# 1_PWR_1.net
KiCad netlist of a schematic drawn in Altium Designer
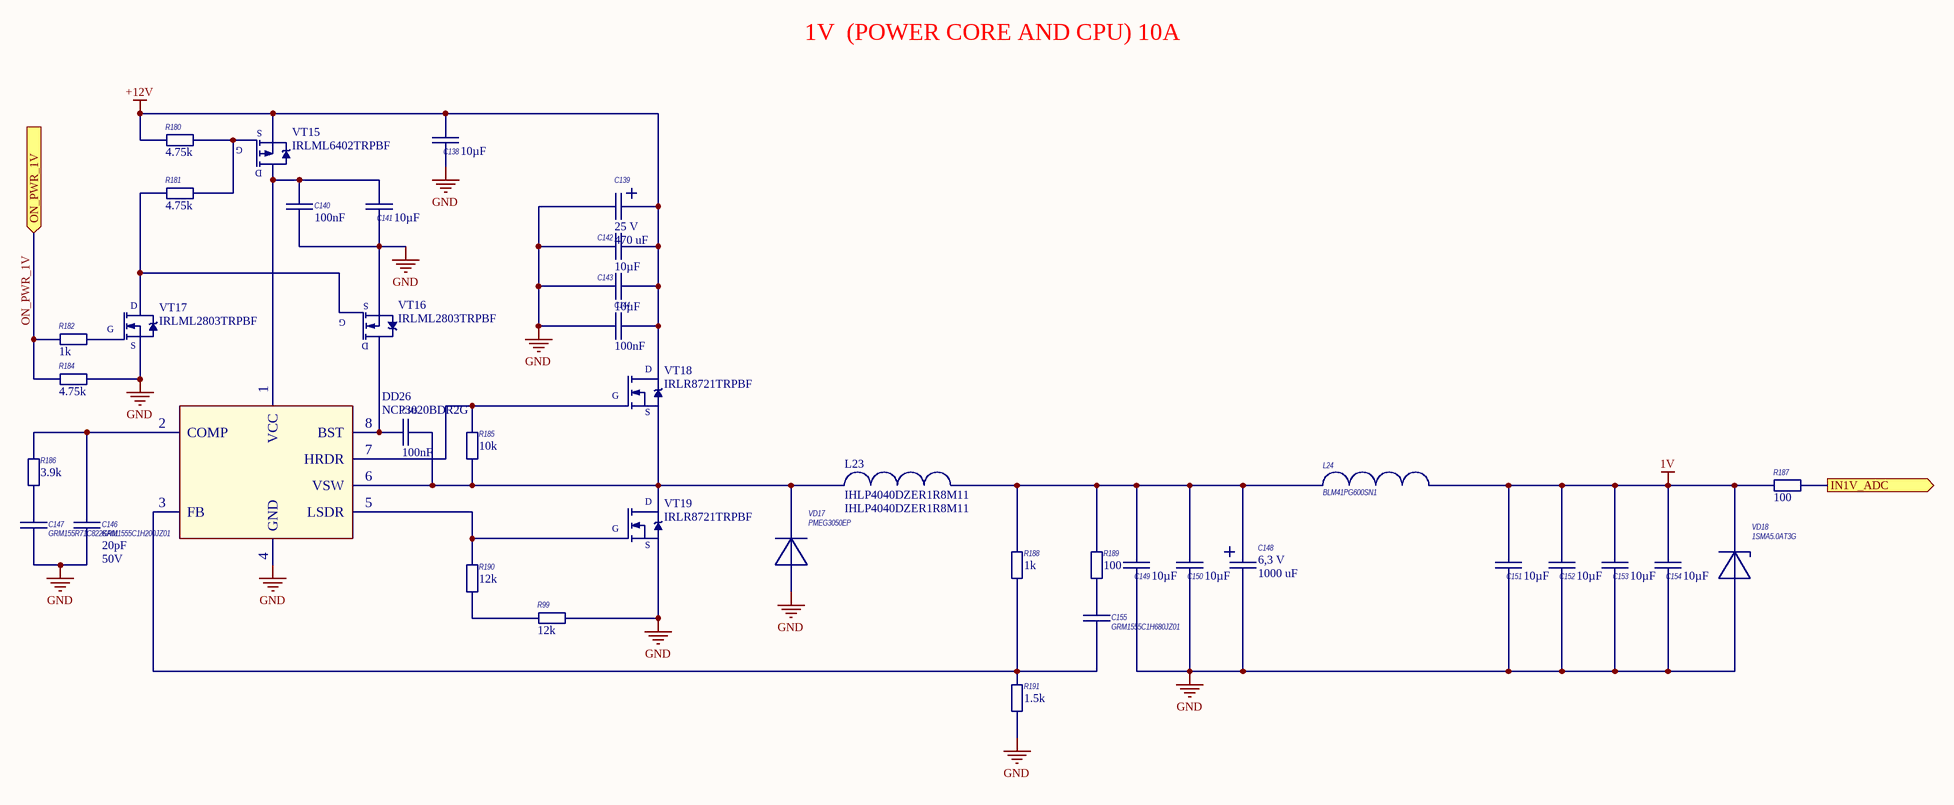
[diagram p0: 1_PWR_1.SchDoc]

(export (version "E")
  (design (tool "Eeschema 10.0.6"))
  (components
    (comp (ref "C138")
      (value "GRM21BR61C106KE15")
      (footprint "CAPC2012[0805]")
      (description "C0805, 10uF 10%, 16V, X5R")
      (fields
        (field (name "MANUFACTURER") "Murata")
        (field (name "TOLERANCE") "±10%")
        (field (name "CAPACITANCE") "10µF")
      )
      (libsource (lib "CAPACITORS") (part "GRM21BR61C106KE15"))
    )
    (comp (ref "C139")
      (value "CA025M0470REG-1010")
      (footprint "CAP SMD 1010")
      (description "Capacitor Aluminium SMD1010, 470uF 25V")
      (fields
        (field (name "MANUFACTURER") "Yageo")
        (field (name "TOLERANCE") "20 %")
        (field (name "VOLTAGE RATING") "25 V")
        (field (name "CAPACITANCE") "470 uF")
      )
      (libsource (lib "CAPACITORS") (part "CA025M0470REG-1010"))
    )
    (comp (ref "C140")
      (value "GRM155R71E104KE14D")
      (footprint "C0402_IPC High Density")
      (description "C0402, 100nF, 25V, X7R")
      (fields
        (field (name "MANUFACTURER") "Murata")
        (field (name "CAPACITANCE") "100nF")
        (field (name "CUSTOMER PART NUMBER") "Конденсатор, 100n, 0402, 25V, X7R, 10%")
      )
      (libsource (lib "CAPACITORS") (part "GRM155R71E104KE14D"))
    )
    (comp (ref "C141")
      (value "GRM21BR61C106KE15")
      (footprint "CAPC2012[0805]")
      (description "C0805, 10uF 10%, 16V, X5R")
      (fields
        (field (name "MANUFACTURER") "Murata")
        (field (name "TOLERANCE") "±10%")
        (field (name "CAPACITANCE") "10µF")
      )
      (libsource (lib "CAPACITORS") (part "GRM21BR61C106KE15"))
    )
    (comp (ref "C142")
      (value "GRM21BR61C106KE15")
      (footprint "CAPC2012[0805]")
      (description "C0805, 10uF 10%, 16V, X5R")
      (fields
        (field (name "MANUFACTURER") "Murata")
        (field (name "TOLERANCE") "±10%")
        (field (name "CAPACITANCE") "10µF")
      )
      (libsource (lib "CAPACITORS") (part "GRM21BR61C106KE15"))
    )
    (comp (ref "C143")
      (value "GRM21BR61C106KE15")
      (footprint "CAPC2012[0805]")
      (description "C0805, 10uF 10%, 16V, X5R")
      (fields
        (field (name "MANUFACTURER") "Murata")
        (field (name "TOLERANCE") "±10%")
        (field (name "CAPACITANCE") "10µF")
      )
      (libsource (lib "CAPACITORS") (part "GRM21BR61C106KE15"))
    )
    (comp (ref "C144")
      (value "GRM155R71E104KE14D")
      (footprint "C0402_IPC High Density")
      (description "C0402, 100nF, 25V, X7R")
      (fields
        (field (name "MANUFACTURER") "Murata")
        (field (name "CAPACITANCE") "100nF")
        (field (name "CUSTOMER PART NUMBER") "Конденсатор, 100n, 0402, 25V, X7R, 10%")
      )
      (libsource (lib "CAPACITORS") (part "GRM155R71E104KE14D"))
    )
    (comp (ref "C145")
      (value "GRM155R71E104KE14D")
      (footprint "C0402_IPC High Density")
      (description "C0402, 100nF, 25V, X7R")
      (fields
        (field (name "CAPACITANCE") "100nF")
        (field (name "CUSTOMER PART NUMBER") "Конденсатор, 100n, 0402, 25V, X7R, 10%")
        (field (name "MANUFACTURER") "Murata")
      )
      (libsource (lib "CAPACITORS") (part "GRM155R71E104KE14D"))
    )
    (comp (ref "C146")
      (value "GRM1555C1H200JZ01")
      (footprint "CAPC1005[0402]")
      (description "C0402, 20pF,  50V, C0G")
      (fields
        (field (name "MANUFACTURER") "Murata")
        (field (name "TOLERANCE") "±5%")
        (field (name "CAPACITANCE") "20pF")
        (field (name "VOLTAGE - RATED") "50V")
      )
      (libsource (lib "CAPACITORS") (part "GRM1555C1H200JZ01"))
    )
    (comp (ref "C147")
      (value "GRM155R71C822KA01")
      (footprint "CAPC1005[0402]")
      (description "C0402, 8.2nF,  50V, X7R")
      (fields (field (name "MANUFACTURER") "Murata") (field (name "TOLERANCE") "10 %"))
      (libsource (lib "CAPACITORS") (part "GRM155R71C822KA01"))
    )
    (comp (ref "C148")
      (value "CA006M1000REG-1010")
      (footprint "CAP SMD 1010")
      (description "Capacitor Aluminium SMD1010, 1000uF 6,3V")
      (fields
        (field (name "MANUFACTURER") "Yageo")
        (field (name "TOLERANCE") "20 %")
        (field (name "VOLTAGE RATING") "6,3 V")
        (field (name "CAPACITANCE") "1000 uF")
      )
      (libsource (lib "CAPACITORS") (part "CA006M1000REG-1010"))
    )
    (comp (ref "C149")
      (value "GRM21BR61C106KE15")
      (footprint "CAPC2012[0805]")
      (description "C0805, 10uF 10%, 16V, X5R")
      (fields
        (field (name "MANUFACTURER") "Murata")
        (field (name "TOLERANCE") "±10%")
        (field (name "CAPACITANCE") "10µF")
      )
      (libsource (lib "CAPACITORS") (part "GRM21BR61C106KE15"))
    )
    (comp (ref "C150")
      (value "GRM21BR61C106KE15")
      (footprint "CAPC2012[0805]")
      (description "C0805, 10uF 10%, 16V, X5R")
      (fields
        (field (name "MANUFACTURER") "Murata")
        (field (name "TOLERANCE") "±10%")
        (field (name "CAPACITANCE") "10µF")
      )
      (libsource (lib "CAPACITORS") (part "GRM21BR61C106KE15"))
    )
    (comp (ref "C151")
      (value "GRM21BR61C106KE15")
      (footprint "CAPC2012[0805]")
      (description "C0805, 10uF 10%, 16V, X5R")
      (fields
        (field (name "MANUFACTURER") "Murata")
        (field (name "TOLERANCE") "±10%")
        (field (name "CAPACITANCE") "10µF")
      )
      (libsource (lib "CAPACITORS") (part "GRM21BR61C106KE15"))
    )
    (comp (ref "C152")
      (value "GRM21BR61C106KE15")
      (footprint "CAPC2012[0805]")
      (description "C0805, 10uF 10%, 16V, X5R")
      (fields
        (field (name "MANUFACTURER") "Murata")
        (field (name "TOLERANCE") "±10%")
        (field (name "CAPACITANCE") "10µF")
      )
      (libsource (lib "CAPACITORS") (part "GRM21BR61C106KE15"))
    )
    (comp (ref "C153")
      (value "GRM21BR61C106KE15")
      (footprint "CAPC2012[0805]")
      (description "C0805, 10uF 10%, 16V, X5R")
      (fields
        (field (name "MANUFACTURER") "Murata")
        (field (name "TOLERANCE") "±10%")
        (field (name "CAPACITANCE") "10µF")
      )
      (libsource (lib "CAPACITORS") (part "GRM21BR61C106KE15"))
    )
    (comp (ref "C154")
      (value "GRM21BR61C106KE15")
      (footprint "CAPC2012[0805]")
      (description "C0805, 10uF 10%, 16V, X5R")
      (fields
        (field (name "MANUFACTURER") "Murata")
        (field (name "TOLERANCE") "±10%")
        (field (name "CAPACITANCE") "10µF")
      )
      (libsource (lib "CAPACITORS") (part "GRM21BR61C106KE15"))
    )
    (comp (ref "C155")
      (value "GRM1555C1H680JZ01")
      (footprint "CAPC1005[0402]")
      (description "C0402, 68pF,  50V, C0G")
      (fields (field (name "TOLERANCE") "±5%") (field (name "MANUFACTURER") "Murata"))
      (libsource (lib "CAPACITORS") (part "GRM1555C1H680JZ01"))
    )
    (comp (ref "DD26")
      (value "NCP3020BDR2G")
      (footprint "751-07_N")
      (description "IC PWM Controller 600 kHz NCP3020BDR2G")
      (fields
        (field (name "MANUFACTURER") "ON Semiconductor")
        (field (name "CUSTOMER PART NUMBER") "Микросхема, NCP3020BDR2G, IC REG CTRLR BUCK, 8-SOIC")
      )
      (libsource (lib "DIGITAL and ANALIG ICs") (part "NCP3020BDR2G"))
    )
    (comp (ref "L23")
      (value "IHLP4040DZER1R8M11")
      (footprint "IHLP4040DZ")
      (description "INDUCTOR 1.8UH 16A")
      (fields
        (field (name "MANUFACTURER") "Vishay Dale")
        (field (name "TOLERANCE") "±20%")
        (field (name "MANUFACTURER PART NUMBER") "IHLP4040DZER1R8M11")
      )
      (libsource (lib "INDUCTORS") (part "IHLP4040DZER1R8M11"))
    )
    (comp (ref "L24")
      (value "BLM41PG600SN1")
      (footprint "INDUCTORS:BLM41P")
      (description "FILTER BLM41 (1806, 6A)")
      (fields
        (field (name "MANUFACTURER") "Murata")
        (field (name "MANUFACTURER PART NUMBER") "BLM41PG600SN1L")
      )
      (libsource (lib "INDUCTORS") (part "BLM41PG600SN1"))
    )
    (comp (ref "R99")
      (value "ERJ-2RKF1202X")
      (footprint "R0402_IPC High Density")
      (description "R0402, 12k 1%")
      (fields
        (field (name "MANUFACTURER") "Panasonic")
        (field (name "TOLERANCE") "±1%")
        (field (name "RESISTANCE (OHMS)") "12k")
      )
      (libsource (lib "RESISTOR") (part "ERJ-2RKF1202X"))
    )
    (comp (ref "R180")
      (value "ERJ-2RKF4751X")
      (footprint "R0402_IPC High Density")
      (description "R0402, 4.75k 1%")
      (fields
        (field (name "TOLERANCE") "±1%")
        (field (name "MANUFACTURER") "Panasonic")
        (field (name "RESISTANCE (OHMS)") "4.75k")
      )
      (libsource (lib "RESISTOR") (part "ERJ-2RKF4751X"))
    )
    (comp (ref "R181")
      (value "ERJ-2RKF4751X")
      (footprint "R0402_IPC High Density")
      (description "R0402, 4.75k 1%")
      (fields
        (field (name "TOLERANCE") "±1%")
        (field (name "MANUFACTURER") "Panasonic")
        (field (name "RESISTANCE (OHMS)") "4.75k")
      )
      (libsource (lib "RESISTOR") (part "ERJ-2RKF4751X"))
    )
    (comp (ref "R182")
      (value "ERJ-2RKF1001X")
      (footprint "R0402_IPC High Density")
      (description "R0402, 1k 1%")
      (fields
        (field (name "MANUFACTURER") "Panasonic")
        (field (name "TOLERANCE") "1 %")
        (field (name "RESISTANCE") "1k")
      )
      (libsource (lib "RESISTOR") (part "ERJ-2RKF1001X"))
    )
    (comp (ref "R184")
      (value "ERJ-2RKF4751X")
      (footprint "R0402_IPC High Density")
      (description "R0402, 4.75k 1%")
      (fields
        (field (name "TOLERANCE") "±1%")
        (field (name "MANUFACTURER") "Panasonic")
        (field (name "RESISTANCE (OHMS)") "4.75k")
      )
      (libsource (lib "RESISTOR") (part "ERJ-2RKF4751X"))
    )
    (comp (ref "R185")
      (value "ERJ-2RKF1002X")
      (footprint "R0402_IPC High Density")
      (description "R0402, 10k 1%")
      (fields
        (field (name "MANUFACTURER") "Panasonic")
        (field (name "TOLERANCE") "1 %")
        (field (name "RESISTANCE") "10k")
      )
      (libsource (lib "RESISTOR") (part "ERJ-2RKF1002X"))
    )
    (comp (ref "R186")
      (value "ERJ-2RKF3901X")
      (footprint "R0402_IPC High Density")
      (description "R0402, 3.9k 1%")
      (fields
        (field (name "MANUFACTURER") "Panasonic")
        (field (name "TOLERANCE") "1 %")
        (field (name "RESISTANCE") "3.9k")
      )
      (libsource (lib "RESISTOR") (part "ERJ-2RKF3901X"))
    )
    (comp (ref "R187")
      (value "ERJ-2RKF1000X")
      (footprint "R0402_IPC High Density")
      (description "R0402, 100R 1%")
      (fields
        (field (name "MANUFACTURER") "Panasonic")
        (field (name "TOLERANCE") "1 %")
        (field (name "RESISTANCE") "100")
      )
      (libsource (lib "RESISTOR") (part "ERJ-2RKF1000X"))
    )
    (comp (ref "R188")
      (value "ERJ-2RKF1001X")
      (footprint "R0402_IPC High Density")
      (description "R0402, 1k 1%")
      (fields
        (field (name "MANUFACTURER") "Panasonic")
        (field (name "TOLERANCE") "1 %")
        (field (name "RESISTANCE") "1k")
      )
      (libsource (lib "RESISTOR") (part "ERJ-2RKF1001X"))
    )
    (comp (ref "R189")
      (value "ERJ-2RKF1000X")
      (footprint "R0402_IPC High Density")
      (description "R0402, 100R 1%")
      (fields
        (field (name "MANUFACTURER") "Panasonic")
        (field (name "TOLERANCE") "1 %")
        (field (name "RESISTANCE") "100")
      )
      (libsource (lib "RESISTOR") (part "ERJ-2RKF1000X"))
    )
    (comp (ref "R190")
      (value "ERJ-2RKF1202X")
      (footprint "R0402_IPC High Density")
      (description "R0402, 12k 1%")
      (fields
        (field (name "MANUFACTURER") "Panasonic")
        (field (name "TOLERANCE") "±1%")
        (field (name "RESISTANCE (OHMS)") "12k")
      )
      (libsource (lib "RESISTOR") (part "ERJ-2RKF1202X"))
    )
    (comp (ref "R191")
      (value "ERJ-2RKF1501X")
      (footprint "R0402_IPC High Density")
      (description "R0402, 1.5k 1%")
      (fields
        (field (name "MANUFACTURER") "Panasonic")
        (field (name "TOLERANCE") "±1%")
        (field (name "RESISTANCE (OHMS)") "1.5k")
      )
      (libsource (lib "RESISTOR") (part "ERJ-2RKF1501X"))
    )
    (comp (ref "VD17")
      (value "PMEG3050EP")
      (footprint "SOD128")
      (description "DIODE 5 A 30 V Schottky barrier rectifier")
      (fields
        (field (name "MANUFACTURER") "NXP Semiconductors")
        (field (name "CUSTOMER PART NUMBER") "Диод, PMEG3050EP.115, DIODE SCHOTTKY 30V 5A, SOD-128")
      )
      (libsource (lib "DIODES") (part "PMEG3050EP"))
    )
    (comp (ref "VD18")
      (value "1SMA5.0AT3G")
      (footprint "DIODES:SMA")
      (description "DIODE TVS 5V 400W SMA")
      (fields
        (field (name "MANUFACTURER") "ON Semiconductor")
        (field (name "CUSTOMER PART NUMBER") "Диод, 1SMA5.0AT3G, TVS DIODE 5VWM 9.2VC SMA")
      )
      (libsource (lib "DIODES") (part "1SMA5.0AT3G"))
    )
    (comp (ref "VT15")
      (value "IRLML6402TRPBF")
      (footprint "SOT-23")
      (description "MOSFET P-CH 20V 3.7A SOT23")
      (fields
        (field (name "MANUFACTURER") "International Rectifier")
        (field (name "RPART NUMBER") "IRLML5203TRPBF ; IRLML6402PbF")
      )
      (libsource (lib "TRANSISTORS") (part "IRLML6402TRPBF"))
    )
    (comp (ref "VT16")
      (value "IRLML2803TRPBF")
      (footprint "SOT-23")
      (description "MOSFET N-CH 30V 1.2A SOT23")
      (fields
        (field (name "MANUFACTURER") "International Rectifier")
        (field (name "RPART NUMBER") "IRLML2402TRPBF ; IRLML2402PBF ; IRLML2803TRPbF")
      )
      (libsource (lib "TRANSISTORS") (part "IRLML2803PBF"))
    )
    (comp (ref "VT17")
      (value "IRLML2803TRPBF")
      (footprint "SOT-23")
      (description "MOSFET N-CH 30V 1.2A SOT23")
      (fields
        (field (name "MANUFACTURER") "International Rectifier")
        (field (name "RPART NUMBER") "IRLML2402TRPBF ; IRLML2402PBF ; IRLML2803TRPbF")
      )
      (libsource (lib "TRANSISTORS") (part "IRLML2803PBF"))
    )
    (comp (ref "VT18")
      (value "IRLR8721TRPBF")
      (footprint "TRANSISTORS:D-PAK (TO-252AA)")
      (description "MOSFET N-CH 30V 65A D-Pak")
      (fields
        (field (name "MANUFACTURER") "International Rectifier")
        (field (name "CUSTOMER PART NUMBER") "Транзистор, IRLR8721TRPBF, MOSFET N-CH 30V 65A, D-Pak")
      )
      (libsource (lib "TRANSISTORS") (part "IRLR8721PbF"))
    )
    (comp (ref "VT19")
      (value "IRLR8721TRPBF")
      (footprint "TRANSISTORS:D-PAK (TO-252AA)")
      (description "MOSFET N-CH 30V 65A D-Pak")
      (fields
        (field (name "MANUFACTURER") "International Rectifier")
        (field (name "CUSTOMER PART NUMBER") "Транзистор, IRLR8721TRPBF, MOSFET N-CH 30V 65A, D-Pak")
      )
      (libsource (lib "TRANSISTORS") (part "IRLR8721PbF"))
    )
  )
  (nets
    (net (code "1") (name "+12V") (class "Default")
      (node (ref "C138") (pin "2") (pintype "passive"))
      (node (ref "C139") (pin "2") (pintype "passive"))
      (node (ref "C142") (pin "2") (pintype "passive"))
      (node (ref "C143") (pin "2") (pintype "passive"))
      (node (ref "C144") (pin "1") (pintype "passive"))
      (node (ref "R180") (pin "2") (pintype "passive"))
      (node (ref "VT15") (pin "2") (pinfunction "S_2") (pintype "passive"))
      (node (ref "VT18") (pin "3") (pinfunction "D_3") (pintype "passive"))
    )
    (net (code "2") (name "/IN1V_ADC") (class "Default") (node (ref "R187") (pin "2") (pintype "passive")))
    (net (code "3") (name "/ON_PWR_1V") (class "Default")
      (node (ref "R182") (pin "1") (pintype "passive"))
      (node (ref "R184") (pin "2") (pintype "passive"))
    )
    (net (code "4") (name "1V") (class "Default")
      (node (ref "C151") (pin "2") (pintype "passive"))
      (node (ref "C152") (pin "2") (pintype "passive"))
      (node (ref "C153") (pin "2") (pintype "passive"))
      (node (ref "C154") (pin "2") (pintype "passive"))
      (node (ref "L24") (pin "2") (pinfunction "2_2") (pintype "passive"))
      (node (ref "R187") (pin "1") (pintype "passive"))
      (node (ref "VD18") (pin "1") (pinfunction "1_1") (pintype "passive"))
    )
    (net (code "5") (name "GND") (class "Default")
      (node (ref "C138") (pin "1") (pintype "passive"))
      (node (ref "C139") (pin "1") (pintype "passive"))
      (node (ref "C140") (pin "1") (pintype "passive"))
      (node (ref "C141") (pin "1") (pintype "passive"))
      (node (ref "C142") (pin "1") (pintype "passive"))
      (node (ref "C143") (pin "1") (pintype "passive"))
      (node (ref "C144") (pin "2") (pintype "passive"))
      (node (ref "C146") (pin "1") (pintype "passive"))
      (node (ref "C147") (pin "1") (pintype "passive"))
      (node (ref "C148") (pin "1") (pintype "passive"))
      (node (ref "C149") (pin "1") (pintype "passive"))
      (node (ref "C150") (pin "1") (pintype "passive"))
      (node (ref "C151") (pin "1") (pintype "passive"))
      (node (ref "C152") (pin "1") (pintype "passive"))
      (node (ref "C153") (pin "1") (pintype "passive"))
      (node (ref "C154") (pin "1") (pintype "passive"))
      (node (ref "DD26") (pin "4") (pinfunction "GND_4") (pintype "passive"))
      (node (ref "R184") (pin "1") (pintype "passive"))
      (node (ref "R191") (pin "1") (pintype "passive"))
      (node (ref "R99") (pin "1") (pintype "passive"))
      (node (ref "VD17") (pin "2") (pinfunction "2_2") (pintype "passive"))
      (node (ref "VD18") (pin "2") (pinfunction "2_2") (pintype "passive"))
      (node (ref "VT16") (pin "2") (pinfunction "S_2") (pintype "passive"))
      (node (ref "VT17") (pin "2") (pinfunction "S_2") (pintype "passive"))
      (node (ref "VT19") (pin "2") (pinfunction "S_2") (pintype "passive"))
    )
    (net (code "6") (name "Net-(C147-Pad2)") (class "Default")
      (node (ref "C147") (pin "2") (pintype "passive"))
      (node (ref "R186") (pin "1") (pintype "passive"))
    )
    (net (code "7") (name "Net-(C148-Pad2)") (class "Default")
      (node (ref "C148") (pin "2") (pintype "passive"))
      (node (ref "C149") (pin "2") (pintype "passive"))
      (node (ref "C150") (pin "2") (pintype "passive"))
      (node (ref "L23") (pin "2") (pinfunction "2_2") (pintype "passive"))
      (node (ref "L24") (pin "1") (pinfunction "1_1") (pintype "passive"))
      (node (ref "R188") (pin "2") (pintype "passive"))
      (node (ref "R189") (pin "2") (pintype "passive"))
    )
    (net (code "8") (name "Net-(C155-Pad2)") (class "Default")
      (node (ref "C155") (pin "2") (pintype "passive"))
      (node (ref "R189") (pin "1") (pintype "passive"))
    )
    (net (code "9") (name "Net-(DD26-BST)") (class "Default")
      (node (ref "C145") (pin "1") (pintype "passive"))
      (node (ref "DD26") (pin "8") (pinfunction "BST_8") (pintype "passive"))
      (node (ref "VT16") (pin "3") (pinfunction "D_3") (pintype "passive"))
    )
    (net (code "10") (name "Net-(DD26-COMP)") (class "Default")
      (node (ref "C146") (pin "2") (pintype "passive"))
      (node (ref "DD26") (pin "2") (pinfunction "COMP_2") (pintype "passive"))
      (node (ref "R186") (pin "2") (pintype "passive"))
    )
    (net (code "11") (name "Net-(DD26-FB)") (class "Default")
      (node (ref "C155") (pin "1") (pintype "passive"))
      (node (ref "DD26") (pin "3") (pinfunction "FB_3") (pintype "passive"))
      (node (ref "R188") (pin "1") (pintype "passive"))
      (node (ref "R191") (pin "2") (pintype "passive"))
    )
    (net (code "12") (name "Net-(DD26-HRDR)") (class "Default")
      (node (ref "DD26") (pin "7") (pinfunction "HRDR_7") (pintype "passive"))
      (node (ref "R185") (pin "2") (pintype "passive"))
      (node (ref "VT18") (pin "1") (pinfunction "G_1") (pintype "passive"))
    )
    (net (code "13") (name "Net-(DD26-LSDR)") (class "Default")
      (node (ref "DD26") (pin "5") (pinfunction "LSDR_5") (pintype "passive"))
      (node (ref "R190") (pin "2") (pintype "passive"))
      (node (ref "VT19") (pin "1") (pinfunction "G_1") (pintype "passive"))
    )
    (net (code "14") (name "Net-(DD26-VCC)") (class "Default")
      (node (ref "C140") (pin "2") (pintype "passive"))
      (node (ref "C141") (pin "2") (pintype "passive"))
      (node (ref "DD26") (pin "1") (pinfunction "VCC_1") (pintype "passive"))
      (node (ref "VT15") (pin "3") (pinfunction "D_3") (pintype "passive"))
    )
    (net (code "15") (name "Net-(DD26-VSW)") (class "Default")
      (node (ref "C145") (pin "2") (pintype "passive"))
      (node (ref "DD26") (pin "6") (pinfunction "VSW_6") (pintype "passive"))
      (node (ref "L23") (pin "1") (pinfunction "1_1") (pintype "passive"))
      (node (ref "R185") (pin "1") (pintype "passive"))
      (node (ref "VD17") (pin "1") (pinfunction "1_1") (pintype "passive"))
      (node (ref "VT18") (pin "2") (pinfunction "S_2") (pintype "passive"))
      (node (ref "VT19") (pin "3") (pinfunction "D_3") (pintype "passive"))
    )
    (net (code "16") (name "Net-(R190-Pad1)") (class "Default")
      (node (ref "R190") (pin "1") (pintype "passive"))
      (node (ref "R99") (pin "2") (pintype "passive"))
    )
    (net (code "17") (name "Net-(VT15-G)") (class "Default")
      (node (ref "R180") (pin "1") (pintype "passive"))
      (node (ref "R181") (pin "1") (pintype "passive"))
      (node (ref "VT15") (pin "1") (pinfunction "G_1") (pintype "passive"))
    )
    (net (code "18") (name "Net-(VT16-G)") (class "Default")
      (node (ref "R181") (pin "2") (pintype "passive"))
      (node (ref "VT16") (pin "1") (pinfunction "G_1") (pintype "passive"))
      (node (ref "VT17") (pin "3") (pinfunction "D_3") (pintype "passive"))
    )
    (net (code "19") (name "Net-(VT17-G)") (class "Default")
      (node (ref "R182") (pin "2") (pintype "passive"))
      (node (ref "VT17") (pin "1") (pinfunction "G_1") (pintype "passive"))
    )
  )
)
